# Top_Layer.net
KiCad netlist of a schematic drawn in Altium Designer
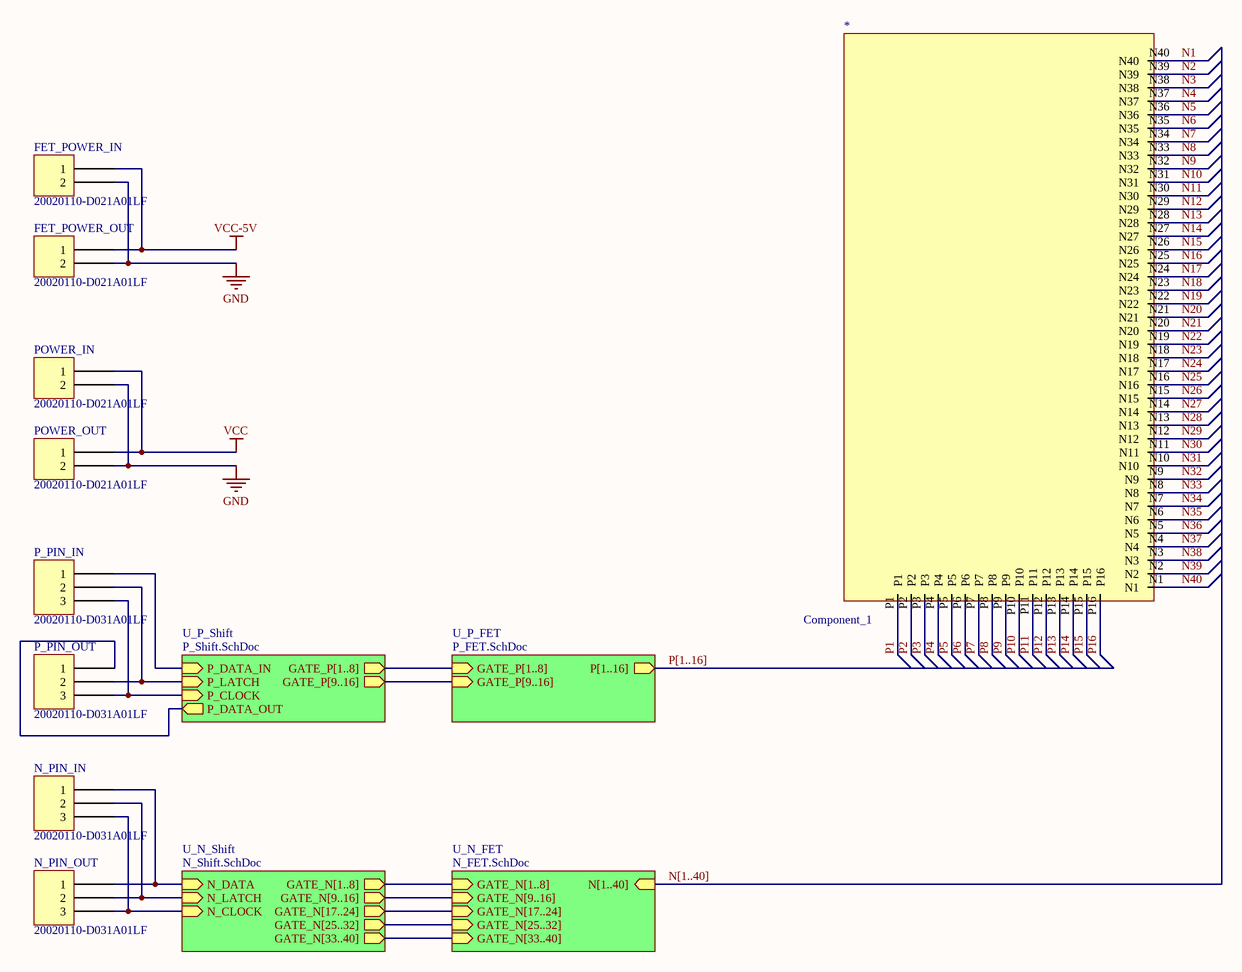
[diagram p0: Top_Layer.SchDoc]

(export (version "E")
  (design (tool "Eeschema 10.0.6"))
  (components
    (comp (ref "*")
      (value "Component_1")
      (footprint "Coils_40x16:PCBComponent_1")
      (libsource (lib "Coils_40x16") (part "Component_1"))
    )
    (comp (ref "FET_POWER_IN")
      (value "20020110-D021A01LF")
      (footprint "FCI 06-381-2PIN")
      (description "TERM BLOCK HDR 2POS R/A 3.81MM")
      (fields (field (name "MANUFACTURER") "FCI") (field (name "VOLTAGE") "300V"))
      (libsource (lib "Celestial Library Database") (part "2 Pin"))
    )
    (comp (ref "FET_POWER_OUT")
      (value "20020110-D021A01LF")
      (footprint "FCI 06-381-2PIN")
      (description "TERM BLOCK HDR 2POS R/A 3.81MM")
      (fields (field (name "MANUFACTURER") "FCI") (field (name "VOLTAGE") "300V"))
      (libsource (lib "Celestial Library Database") (part "2 Pin"))
    )
    (comp (ref "N_PIN_IN")
      (value "20020110-D031A01LF")
      (footprint "FCI 06-381-3PIN")
      (description "TERM BLOCK HDR 3POS R/A 3.81MM")
      (fields (field (name "MANUFACTURER") "FCI") (field (name "VOLTAGE") "300V"))
      (libsource (lib "Celestial Library Database") (part "3 Pin"))
    )
    (comp (ref "N_PIN_OUT")
      (value "20020110-D031A01LF")
      (footprint "FCI 06-381-3PIN")
      (description "TERM BLOCK HDR 3POS R/A 3.81MM")
      (fields (field (name "MANUFACTURER") "FCI") (field (name "VOLTAGE") "300V"))
      (libsource (lib "Celestial Library Database") (part "3 Pin"))
    )
    (comp (ref "POWER_IN")
      (value "20020110-D021A01LF")
      (footprint "FCI 06-381-2PIN")
      (description "TERM BLOCK HDR 2POS R/A 3.81MM")
      (fields (field (name "MANUFACTURER") "FCI") (field (name "VOLTAGE") "300V"))
      (libsource (lib "Celestial Library Database") (part "2 Pin"))
    )
    (comp (ref "POWER_OUT")
      (value "20020110-D021A01LF")
      (footprint "FCI 06-381-2PIN")
      (description "TERM BLOCK HDR 2POS R/A 3.81MM")
      (fields (field (name "MANUFACTURER") "FCI") (field (name "VOLTAGE") "300V"))
      (libsource (lib "Celestial Library Database") (part "2 Pin"))
    )
    (comp (ref "P_PIN_IN")
      (value "20020110-D031A01LF")
      (footprint "FCI 06-381-3PIN")
      (description "TERM BLOCK HDR 3POS R/A 3.81MM")
      (fields (field (name "MANUFACTURER") "FCI") (field (name "VOLTAGE") "300V"))
      (libsource (lib "Celestial Library Database") (part "3 Pin"))
    )
    (comp (ref "P_PIN_OUT")
      (value "20020110-D031A01LF")
      (footprint "FCI 06-381-3PIN")
      (description "TERM BLOCK HDR 3POS R/A 3.81MM")
      (fields (field (name "MANUFACTURER") "FCI") (field (name "VOLTAGE") "300V"))
      (libsource (lib "Celestial Library Database") (part "3 Pin"))
    )
  )
  (nets
    (net (code "8") (name "/N1") (class "Default")
      (node (ref "*") (pin "N40") (pinfunction "N40_N40") (pintype "passive"))
    )
    (net (code "9") (name "/N2") (class "Default")
      (node (ref "*") (pin "N39") (pinfunction "N39_N39") (pintype "passive"))
    )
    (net (code "10") (name "/N3") (class "Default")
      (node (ref "*") (pin "N38") (pinfunction "N38_N38") (pintype "passive"))
    )
    (net (code "11") (name "/N4") (class "Default")
      (node (ref "*") (pin "N37") (pinfunction "N37_N37") (pintype "passive"))
    )
    (net (code "12") (name "/N5") (class "Default")
      (node (ref "*") (pin "N36") (pinfunction "N36_N36") (pintype "passive"))
    )
    (net (code "13") (name "/N6") (class "Default")
      (node (ref "*") (pin "N35") (pinfunction "N35_N35") (pintype "passive"))
    )
    (net (code "14") (name "/N7") (class "Default")
      (node (ref "*") (pin "N34") (pinfunction "N34_N34") (pintype "passive"))
    )
    (net (code "15") (name "/N8") (class "Default")
      (node (ref "*") (pin "N33") (pinfunction "N33_N33") (pintype "passive"))
    )
    (net (code "16") (name "/N9") (class "Default")
      (node (ref "*") (pin "N32") (pinfunction "N32_N32") (pintype "passive"))
    )
    (net (code "17") (name "/N10") (class "Default")
      (node (ref "*") (pin "N31") (pinfunction "N31_N31") (pintype "passive"))
    )
    (net (code "18") (name "/N11") (class "Default")
      (node (ref "*") (pin "N30") (pinfunction "N30_N30") (pintype "passive"))
    )
    (net (code "19") (name "/N12") (class "Default")
      (node (ref "*") (pin "N29") (pinfunction "N29_N29") (pintype "passive"))
    )
    (net (code "20") (name "/N13") (class "Default")
      (node (ref "*") (pin "N28") (pinfunction "N28_N28") (pintype "passive"))
    )
    (net (code "21") (name "/N14") (class "Default")
      (node (ref "*") (pin "N27") (pinfunction "N27_N27") (pintype "passive"))
    )
    (net (code "22") (name "/N15") (class "Default")
      (node (ref "*") (pin "N26") (pinfunction "N26_N26") (pintype "passive"))
    )
    (net (code "23") (name "/N16") (class "Default")
      (node (ref "*") (pin "N25") (pinfunction "N25_N25") (pintype "passive"))
    )
    (net (code "24") (name "/N17") (class "Default")
      (node (ref "*") (pin "N24") (pinfunction "N24_N24") (pintype "passive"))
    )
    (net (code "25") (name "/N18") (class "Default")
      (node (ref "*") (pin "N23") (pinfunction "N23_N23") (pintype "passive"))
    )
    (net (code "26") (name "/N19") (class "Default")
      (node (ref "*") (pin "N22") (pinfunction "N22_N22") (pintype "passive"))
    )
    (net (code "27") (name "/N20") (class "Default")
      (node (ref "*") (pin "N21") (pinfunction "N21_N21") (pintype "passive"))
    )
    (net (code "28") (name "/N21") (class "Default")
      (node (ref "*") (pin "N20") (pinfunction "N20_N20") (pintype "passive"))
    )
    (net (code "29") (name "/N22") (class "Default")
      (node (ref "*") (pin "N19") (pinfunction "N19_N19") (pintype "passive"))
    )
    (net (code "30") (name "/N23") (class "Default")
      (node (ref "*") (pin "N18") (pinfunction "N18_N18") (pintype "passive"))
    )
    (net (code "31") (name "/N24") (class "Default")
      (node (ref "*") (pin "N17") (pinfunction "N17_N17") (pintype "passive"))
    )
    (net (code "32") (name "/N25") (class "Default")
      (node (ref "*") (pin "N16") (pinfunction "N16_N16") (pintype "passive"))
    )
    (net (code "33") (name "/N26") (class "Default")
      (node (ref "*") (pin "N15") (pinfunction "N15_N15") (pintype "passive"))
    )
    (net (code "34") (name "/N27") (class "Default")
      (node (ref "*") (pin "N14") (pinfunction "N14_N14") (pintype "passive"))
    )
    (net (code "35") (name "/N28") (class "Default")
      (node (ref "*") (pin "N13") (pinfunction "N13_N13") (pintype "passive"))
    )
    (net (code "36") (name "/N29") (class "Default")
      (node (ref "*") (pin "N12") (pinfunction "N12_N12") (pintype "passive"))
    )
    (net (code "37") (name "/N30") (class "Default")
      (node (ref "*") (pin "N11") (pinfunction "N11_N11") (pintype "passive"))
    )
    (net (code "38") (name "/N31") (class "Default")
      (node (ref "*") (pin "N10") (pinfunction "N10_N10") (pintype "passive"))
    )
    (net (code "39") (name "/N32") (class "Default")
      (node (ref "*") (pin "N9") (pinfunction "N9_N9") (pintype "passive"))
    )
    (net (code "40") (name "/N33") (class "Default")
      (node (ref "*") (pin "N8") (pinfunction "N8_N8") (pintype "passive"))
    )
    (net (code "41") (name "/N34") (class "Default")
      (node (ref "*") (pin "N7") (pinfunction "N7_N7") (pintype "passive"))
    )
    (net (code "42") (name "/N35") (class "Default")
      (node (ref "*") (pin "N6") (pinfunction "N6_N6") (pintype "passive"))
    )
    (net (code "43") (name "/N36") (class "Default")
      (node (ref "*") (pin "N5") (pinfunction "N5_N5") (pintype "passive"))
    )
    (net (code "44") (name "/N37") (class "Default")
      (node (ref "*") (pin "N4") (pinfunction "N4_N4") (pintype "passive"))
    )
    (net (code "45") (name "/N38") (class "Default")
      (node (ref "*") (pin "N3") (pinfunction "N3_N3") (pintype "passive"))
    )
    (net (code "46") (name "/N39") (class "Default")
      (node (ref "*") (pin "N2") (pinfunction "N2_N2") (pintype "passive"))
    )
    (net (code "47") (name "/N40") (class "Default")
      (node (ref "*") (pin "N1") (pinfunction "N1_N1") (pintype "passive"))
    )
    (net (code "49") (name "/N_CLOCK") (class "Default")
      (node (ref "N_PIN_IN") (pin "3") (pinfunction "3_3") (pintype "passive"))
      (node (ref "N_PIN_OUT") (pin "3") (pinfunction "3_3") (pintype "passive"))
    )
    (net (code "50") (name "/N_DATA") (class "Default")
      (node (ref "N_PIN_IN") (pin "1") (pinfunction "1_1") (pintype "passive"))
      (node (ref "N_PIN_OUT") (pin "1") (pinfunction "1_1") (pintype "passive"))
    )
    (net (code "51") (name "/N_LATCH") (class "Default")
      (node (ref "N_PIN_IN") (pin "2") (pinfunction "2_2") (pintype "passive"))
      (node (ref "N_PIN_OUT") (pin "2") (pinfunction "2_2") (pintype "passive"))
    )
    (net (code "52") (name "/P1") (class "Default")
      (node (ref "*") (pin "P1") (pinfunction "P1_P1") (pintype "passive"))
    )
    (net (code "53") (name "/P2") (class "Default")
      (node (ref "*") (pin "P2") (pinfunction "P2_P2") (pintype "passive"))
    )
    (net (code "54") (name "/P3") (class "Default")
      (node (ref "*") (pin "P3") (pinfunction "P3_P3") (pintype "passive"))
    )
    (net (code "55") (name "/P4") (class "Default")
      (node (ref "*") (pin "P4") (pinfunction "P4_P4") (pintype "passive"))
    )
    (net (code "56") (name "/P5") (class "Default")
      (node (ref "*") (pin "P5") (pinfunction "P5_P5") (pintype "passive"))
    )
    (net (code "57") (name "/P6") (class "Default")
      (node (ref "*") (pin "P6") (pinfunction "P6_P6") (pintype "passive"))
    )
    (net (code "58") (name "/P7") (class "Default")
      (node (ref "*") (pin "P7") (pinfunction "P7_P7") (pintype "passive"))
    )
    (net (code "59") (name "/P8") (class "Default")
      (node (ref "*") (pin "P8") (pinfunction "P8_P8") (pintype "passive"))
    )
    (net (code "60") (name "/P9") (class "Default")
      (node (ref "*") (pin "P9") (pinfunction "P9_P9") (pintype "passive"))
    )
    (net (code "61") (name "/P10") (class "Default")
      (node (ref "*") (pin "P10") (pinfunction "P10_P10") (pintype "passive"))
    )
    (net (code "62") (name "/P11") (class "Default")
      (node (ref "*") (pin "P11") (pinfunction "P11_P11") (pintype "passive"))
    )
    (net (code "63") (name "/P12") (class "Default")
      (node (ref "*") (pin "P12") (pinfunction "P12_P12") (pintype "passive"))
    )
    (net (code "64") (name "/P13") (class "Default")
      (node (ref "*") (pin "P13") (pinfunction "P13_P13") (pintype "passive"))
    )
    (net (code "65") (name "/P14") (class "Default")
      (node (ref "*") (pin "P14") (pinfunction "P14_P14") (pintype "passive"))
    )
    (net (code "66") (name "/P15") (class "Default")
      (node (ref "*") (pin "P15") (pinfunction "P15_P15") (pintype "passive"))
    )
    (net (code "67") (name "/P16") (class "Default")
      (node (ref "*") (pin "P16") (pinfunction "P16_P16") (pintype "passive"))
    )
    (net (code "69") (name "/P_CLOCK") (class "Default")
      (node (ref "P_PIN_IN") (pin "3") (pinfunction "3_3") (pintype "passive"))
      (node (ref "P_PIN_OUT") (pin "3") (pinfunction "3_3") (pintype "passive"))
    )
    (net (code "70") (name "/P_DATA_IN") (class "Default")
      (node (ref "P_PIN_IN") (pin "1") (pinfunction "1_1") (pintype "passive"))
    )
    (net (code "71") (name "/P_DATA_OUT") (class "Default")
      (node (ref "P_PIN_OUT") (pin "1") (pinfunction "1_1") (pintype "passive"))
    )
    (net (code "72") (name "/P_LATCH") (class "Default")
      (node (ref "P_PIN_IN") (pin "2") (pinfunction "2_2") (pintype "passive"))
      (node (ref "P_PIN_OUT") (pin "2") (pinfunction "2_2") (pintype "passive"))
    )
    (net (code "73") (name "GND") (class "Default")
      (node (ref "FET_POWER_IN") (pin "2") (pinfunction "2_2") (pintype "passive"))
      (node (ref "FET_POWER_OUT") (pin "2") (pinfunction "2_2") (pintype "passive"))
      (node (ref "POWER_IN") (pin "2") (pinfunction "2_2") (pintype "passive"))
      (node (ref "POWER_OUT") (pin "2") (pinfunction "2_2") (pintype "passive"))
    )
    (net (code "74") (name "VCC") (class "Default")
      (node (ref "POWER_IN") (pin "1") (pinfunction "1_1") (pintype "passive"))
      (node (ref "POWER_OUT") (pin "1") (pinfunction "1_1") (pintype "passive"))
    )
    (net (code "75") (name "VCC-5V") (class "Default")
      (node (ref "FET_POWER_IN") (pin "1") (pinfunction "1_1") (pintype "passive"))
      (node (ref "FET_POWER_OUT") (pin "1") (pinfunction "1_1") (pintype "passive"))
    )
  )
)
